# NG2094_Power_Supply.net
KiCad netlist of a schematic drawn in Altium Designer
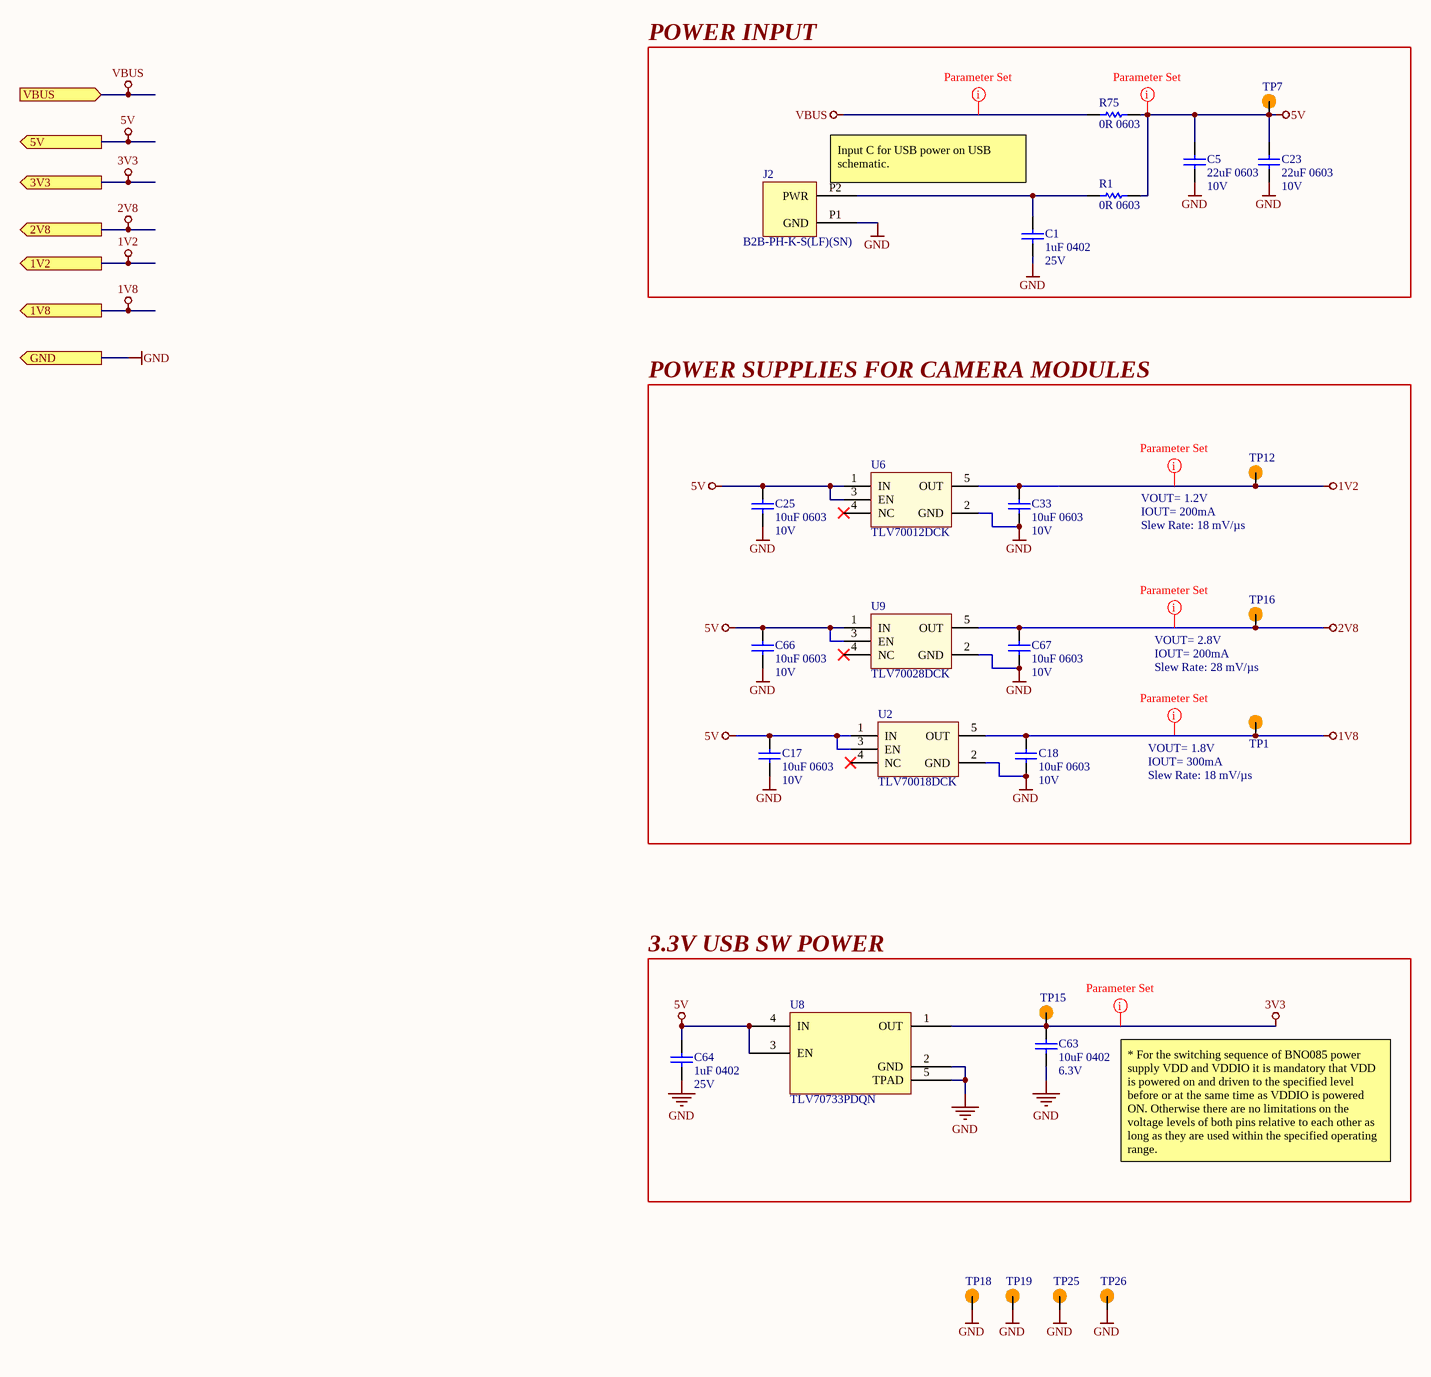
[diagram p0: NG2094_Power_Supply.SchDoc]

(export (version "E")
  (design (tool "Eeschema 10.0.6"))
  (components
    (comp (ref "C1")
      (value "1uF 0402")
      (footprint "CAP_Altium_Vault_Generic:CAPC0402(1005)70_L")
      (description "CAP CER 1UF 25V X5R 0402 10%")
      (fields
        (field (name "TOLERANCE") "10%")
        (field (name "VOLTAGE") "25V")
        (field (name "VOLTAGE RATING") "25V")
      )
      (libsource (lib "LuxonisMaster") (part "GRM155R61E105KA12D"))
    )
    (comp (ref "C5")
      (value "22uF 0603")
      (footprint "CAP_Altium_Vault_Generic:CAPC0603(1608)100_L")
      (description "CAP CER 22UF 10V X5R 0603 20%")
      (fields (field (name "TOLERANCE") "20%") (field (name "VOLTAGE RATING") "10V"))
      (libsource (lib "LuxonisMaster") (part "GRM188R61A226ME15D"))
    )
    (comp (ref "C17")
      (value "10uF 0603")
      (footprint "CAP_Altium_Vault_Generic:CAPC0603(1608)100_L")
      (description "CAP CER 10UF 10V X5R 0603 20%")
      (fields (field (name "TOLERANCE") "20%") (field (name "VOLTAGE RATING") "10V"))
      (libsource (lib "LuxonisMaster") (part "GRM188R61A106ME69D"))
    )
    (comp (ref "C18")
      (value "10uF 0603")
      (footprint "CAP_Altium_Vault_Generic:CAPC0603(1608)100_L")
      (description "CAP CER 10UF 10V X5R 0603 20%")
      (fields (field (name "TOLERANCE") "20%") (field (name "VOLTAGE RATING") "10V"))
      (libsource (lib "LuxonisMaster") (part "GRM188R61A106ME69D"))
    )
    (comp (ref "C23")
      (value "22uF 0603")
      (footprint "CAP_Altium_Vault_Generic:CAPC0603(1608)100_L")
      (description "CAP CER 22UF 10V X5R 0603 20%")
      (fields (field (name "TOLERANCE") "20%") (field (name "VOLTAGE RATING") "10V"))
      (libsource (lib "LuxonisMaster") (part "GRM188R61A226ME15D"))
    )
    (comp (ref "C25")
      (value "10uF 0603")
      (footprint "CAP_Altium_Vault_Generic:CAPC0603(1608)100_L")
      (description "CAP CER 10UF 10V X5R 0603 20%")
      (fields (field (name "TOLERANCE") "20%") (field (name "VOLTAGE RATING") "10V"))
      (libsource (lib "LuxonisMaster") (part "GRM188R61A106ME69D"))
    )
    (comp (ref "C33")
      (value "10uF 0603")
      (footprint "CAP_Altium_Vault_Generic:CAPC0603(1608)100_L")
      (description "CAP CER 10UF 10V X5R 0603 20%")
      (fields (field (name "TOLERANCE") "20%") (field (name "VOLTAGE RATING") "10V"))
      (libsource (lib "LuxonisMaster") (part "GRM188R61A106ME69D"))
    )
    (comp (ref "C63")
      (value "10uF 0402")
      (footprint "CAP_Altium_Vault_Generic:CAPC0402(1005)70_L")
      (description "CAP CER 10UF 6.3V X5R 0402 20%")
      (fields (field (name "TOLERANCE") "20%") (field (name "VOLTAGE RATING") "6.3V"))
      (libsource (lib "LuxonisMaster") (part "GRM155R60J106ME15D"))
    )
    (comp (ref "C64")
      (value "1uF 0402")
      (footprint "CAP_Altium_Vault_Generic:CAPC0402(1005)70_L")
      (description "CAP CER 1UF 25V X5R 0402 10%")
      (fields
        (field (name "TOLERANCE") "10%")
        (field (name "VOLTAGE") "25V")
        (field (name "VOLTAGE RATING") "25V")
      )
      (libsource (lib "LuxonisMaster") (part "GRM155R61E105KA12D"))
    )
    (comp (ref "C66")
      (value "10uF 0603")
      (footprint "CAP_Altium_Vault_Generic:CAPC0603(1608)100_L")
      (description "CAP CER 10UF 10V X5R 0603 20%")
      (fields (field (name "TOLERANCE") "20%") (field (name "VOLTAGE RATING") "10V"))
      (libsource (lib "LuxonisMaster") (part "GRM188R61A106ME69D"))
    )
    (comp (ref "C67")
      (value "10uF 0603")
      (footprint "CAP_Altium_Vault_Generic:CAPC0603(1608)100_L")
      (description "CAP CER 10UF 10V X5R 0603 20%")
      (fields (field (name "TOLERANCE") "20%") (field (name "VOLTAGE RATING") "10V"))
      (libsource (lib "LuxonisMaster") (part "GRM188R61A106ME69D"))
    )
    (comp (ref "J2")
      (value "B2B-PH-K-S(LF)(SN)")
      (footprint "LuxonisMaster:B2B-PH-K-S(LF)(SN)")
      (description "CONN HEADER VERT 2POS 2MM")
      (libsource (lib "LuxonisMaster") (part "B2B-PH-K-S(LF)(SN)"))
    )
    (comp (ref "R1")
      (value "0R 0603")
      (footprint "RES_Altium_Vault_Generic:RESC0603(1608)_L")
      (fields (field (name "TOLERANCE") "5%"))
      (libsource (lib "LuxonisMaster") (part "CRCW06030000Z0EA"))
    )
    (comp (ref "R75")
      (value "0R 0603")
      (footprint "RES_Altium_Vault_Generic:RESC0603(1608)_L")
      (fields (field (name "TOLERANCE") "5%"))
      (libsource (lib "LuxonisMaster") (part "CRCW06030000Z0EA"))
    )
    (comp (ref "TP1")
      (value "TP075_150_NS")
      (footprint "LuxonisMaster:TP075_150_NS")
      (libsource (lib "LuxonisMaster") (part "TEST_POINT"))
    )
    (comp (ref "TP7")
      (value "TP100_200_NS")
      (footprint "LuxonisMaster:TP100_200_NS")
      (libsource (lib "LuxonisMaster") (part "TEST_POINT"))
    )
    (comp (ref "TP12")
      (value "TP100_200_NS")
      (footprint "LuxonisMaster:TP100_200_NS")
      (libsource (lib "LuxonisMaster") (part "TEST_POINT"))
    )
    (comp (ref "TP15")
      (value "TP100_200_NS")
      (footprint "LuxonisMaster:TP100_200_NS")
      (libsource (lib "LuxonisMaster") (part "TEST_POINT"))
    )
    (comp (ref "TP16")
      (value "TP100_200_NS")
      (footprint "LuxonisMaster:TP100_200_NS")
      (libsource (lib "LuxonisMaster") (part "TEST_POINT"))
    )
    (comp (ref "TP18")
      (value "TP100_200_NS")
      (footprint "LuxonisMaster:TP100_200_NS")
      (libsource (lib "LuxonisMaster") (part "TEST_POINT"))
    )
    (comp (ref "TP19")
      (value "TP100_200_NS")
      (footprint "LuxonisMaster:TP100_200_NS")
      (libsource (lib "LuxonisMaster") (part "TEST_POINT"))
    )
    (comp (ref "TP25")
      (value "TP100_200_NS")
      (footprint "LuxonisMaster:TP100_200_NS")
      (libsource (lib "LuxonisMaster") (part "TEST_POINT"))
    )
    (comp (ref "TP26")
      (value "TP100_200_NS")
      (footprint "LuxonisMaster:TP100_200_NS")
      (libsource (lib "LuxonisMaster") (part "TEST_POINT"))
    )
    (comp (ref "U2")
      (value "TLV70018DCK")
      (footprint "LuxonisMaster:TLV70018DCK")
      (description "IC REG LINEAR 1.8V 200MA SC70-5 Linear Voltage Regulator IC  1 Output  200mA SC-70-5")
      (libsource (lib "LuxonisMaster") (part "TLV70018DCK"))
    )
    (comp (ref "U6")
      (value "TLV70012DCK")
      (footprint "LuxonisMaster:TLV70012DCK")
      (description "IC REG LINEAR 1.2V 200MA SC70-5")
      (libsource (lib "LuxonisMaster") (part "TLV70012DCK"))
    )
    (comp (ref "U8")
      (value "TLV70733PDQN")
      (footprint "LuxonisMaster:TLV70733PDQN")
      (description "IC REG LINEAR 3.3V 200MA 4X2SON Linear Voltage Regulator IC  1 Output  200mA 4-X2SON (1x1)")
      (libsource (lib "LuxonisMaster") (part "TLV70733PDQN"))
    )
    (comp (ref "U9")
      (value "TLV70028DCK")
      (footprint "LuxonisMaster:TLV70028DCK")
      (description "IC REG LINEAR 2.8V 200MA SC70-5 Linear Voltage Regulator IC  1 Output  200mA SC-70-5")
      (libsource (lib "LuxonisMaster") (part "TLV70028DCK"))
    )
  )
  (nets
    (net (code "1") (name "1V2") (class "Default")
      (node (ref "C33") (pin "2") (pinfunction "2_2") (pintype "passive"))
      (node (ref "TP12") (pin "1") (pintype "passive"))
      (node (ref "U6") (pin "5") (pinfunction "OUT_5") (pintype "passive"))
    )
    (net (code "2") (name "1V8") (class "Default")
      (node (ref "C18") (pin "2") (pinfunction "2_2") (pintype "passive"))
      (node (ref "TP1") (pin "1") (pintype "passive"))
      (node (ref "U2") (pin "5") (pinfunction "OUT_5") (pintype "passive"))
    )
    (net (code "3") (name "2V8") (class "Default")
      (node (ref "C67") (pin "2") (pinfunction "2_2") (pintype "passive"))
      (node (ref "TP16") (pin "1") (pintype "passive"))
      (node (ref "U9") (pin "5") (pinfunction "OUT_5") (pintype "passive"))
    )
    (net (code "4") (name "3V3") (class "Default")
      (node (ref "C63") (pin "2") (pinfunction "2_2") (pintype "passive"))
      (node (ref "TP15") (pin "1") (pintype "passive"))
      (node (ref "U8") (pin "1") (pinfunction "OUT_1") (pintype "power_in"))
    )
    (net (code "5") (name "5V") (class "Default")
      (node (ref "C17") (pin "2") (pinfunction "2_2") (pintype "passive"))
      (node (ref "C23") (pin "2") (pinfunction "2_2") (pintype "passive"))
      (node (ref "C25") (pin "2") (pinfunction "2_2") (pintype "passive"))
      (node (ref "C5") (pin "2") (pinfunction "2_2") (pintype "passive"))
      (node (ref "C64") (pin "2") (pinfunction "2_2") (pintype "passive"))
      (node (ref "C66") (pin "2") (pinfunction "2_2") (pintype "passive"))
      (node (ref "R1") (pin "2") (pinfunction "2_2") (pintype "passive"))
      (node (ref "R75") (pin "2") (pinfunction "2_2") (pintype "passive"))
      (node (ref "TP7") (pin "1") (pintype "passive"))
      (node (ref "U2") (pin "1") (pinfunction "IN_1") (pintype "passive"))
      (node (ref "U2") (pin "3") (pinfunction "EN_3") (pintype "passive"))
      (node (ref "U6") (pin "1") (pinfunction "IN_1") (pintype "passive"))
      (node (ref "U6") (pin "3") (pinfunction "EN_3") (pintype "passive"))
      (node (ref "U8") (pin "3") (pinfunction "EN_3") (pintype "power_in"))
      (node (ref "U8") (pin "4") (pinfunction "IN_4") (pintype "power_in"))
      (node (ref "U9") (pin "1") (pinfunction "IN_1") (pintype "passive"))
      (node (ref "U9") (pin "3") (pinfunction "EN_3") (pintype "passive"))
    )
    (net (code "6") (name "GND") (class "Default")
      (node (ref "C1") (pin "1") (pinfunction "1_1") (pintype "passive"))
      (node (ref "C17") (pin "1") (pinfunction "1_1") (pintype "passive"))
      (node (ref "C18") (pin "1") (pinfunction "1_1") (pintype "passive"))
      (node (ref "C23") (pin "1") (pinfunction "1_1") (pintype "passive"))
      (node (ref "C25") (pin "1") (pinfunction "1_1") (pintype "passive"))
      (node (ref "C33") (pin "1") (pinfunction "1_1") (pintype "passive"))
      (node (ref "C5") (pin "1") (pinfunction "1_1") (pintype "passive"))
      (node (ref "C63") (pin "1") (pinfunction "1_1") (pintype "passive"))
      (node (ref "C64") (pin "1") (pinfunction "1_1") (pintype "passive"))
      (node (ref "C66") (pin "1") (pinfunction "1_1") (pintype "passive"))
      (node (ref "C67") (pin "1") (pinfunction "1_1") (pintype "passive"))
      (node (ref "J2") (pin "P1") (pinfunction "GND_P1") (pintype "passive"))
      (node (ref "TP18") (pin "1") (pintype "passive"))
      (node (ref "TP19") (pin "1") (pintype "passive"))
      (node (ref "TP25") (pin "1") (pintype "passive"))
      (node (ref "TP26") (pin "1") (pintype "passive"))
      (node (ref "U2") (pin "2") (pinfunction "GND_2") (pintype "passive"))
      (node (ref "U6") (pin "2") (pinfunction "GND_2") (pintype "passive"))
      (node (ref "U8") (pin "2") (pinfunction "GND_2") (pintype "power_in"))
      (node (ref "U8") (pin "5") (pinfunction "TPAD_5") (pintype "passive"))
      (node (ref "U9") (pin "2") (pinfunction "GND_2") (pintype "passive"))
    )
    (net (code "7") (name "Net-(J2-PWR)") (class "Default")
      (node (ref "C1") (pin "2") (pinfunction "2_2") (pintype "passive"))
      (node (ref "J2") (pin "P2") (pinfunction "PWR_P2") (pintype "passive"))
      (node (ref "R1") (pin "1") (pinfunction "1_1") (pintype "passive"))
    )
    (net (code "8") (name "VBUS") (class "Default")
      (node (ref "R75") (pin "1") (pinfunction "1_1") (pintype "passive"))
    )
    (net (code "9") (name "unconnected-(U2-NC-Pad4)") (class "Default")
      (node (ref "U2") (pin "4") (pinfunction "NC_4") (pintype "passive+no_connect"))
    )
    (net (code "10") (name "unconnected-(U6-NC-Pad4)") (class "Default")
      (node (ref "U6") (pin "4") (pinfunction "NC_4") (pintype "passive+no_connect"))
    )
    (net (code "11") (name "unconnected-(U9-NC-Pad4)") (class "Default")
      (node (ref "U9") (pin "4") (pinfunction "NC_4") (pintype "passive+no_connect"))
    )
  )
)
